# gravador.net
KiCad netlist of a schematic drawn in EAGLE
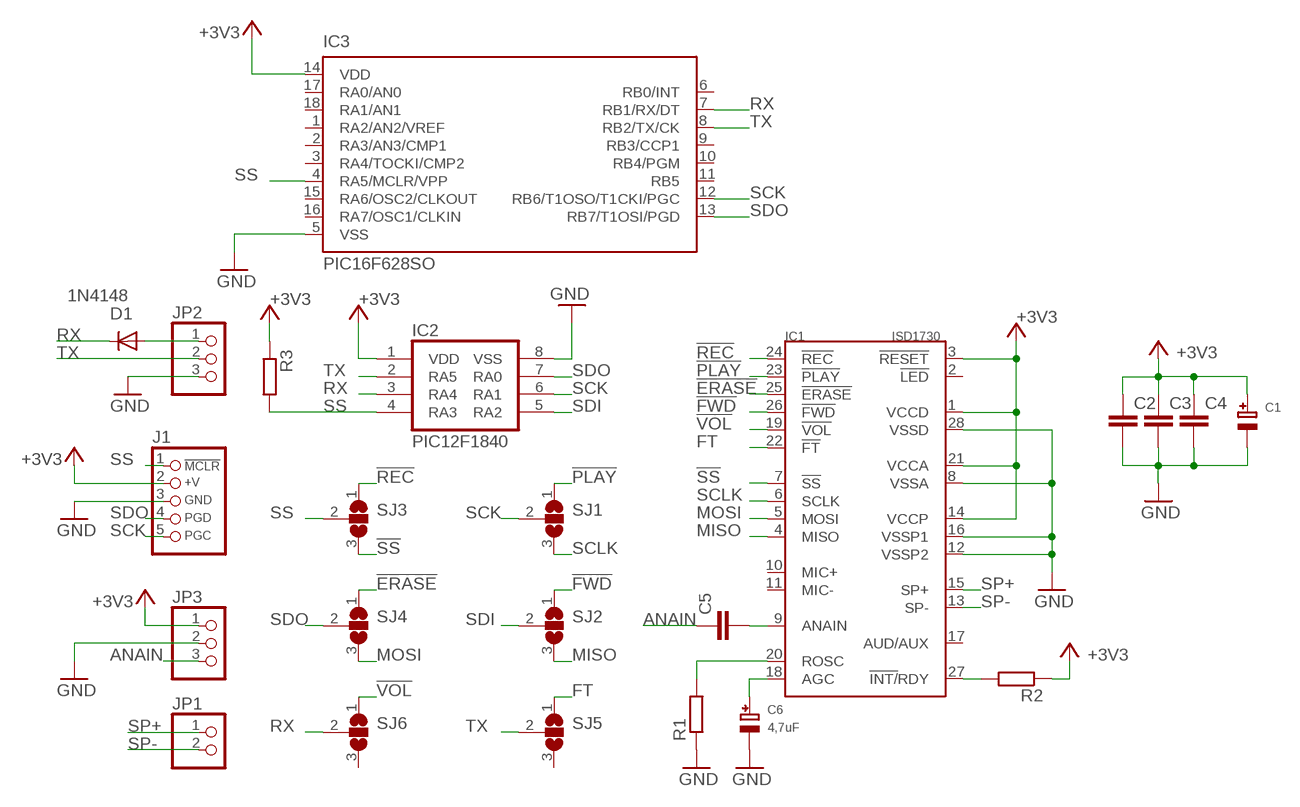
[diagram p0: schematic, sheet 1]

(export (version "E")
  (design (tool "Eeschema 10.0.6"))
  (components
    (comp (ref "C1")
      (value "CAP_ELECTROLYTICPTH_3.5MMGRID_8MMDIA")
      (footprint "eagle-import:CELEC_3.5MM_8MM")
      (libsource (lib "eagle-import") (part "CAP_ELECTROLYTICPTH_3.5MMGRID_8MMDIA"))
    )
    (comp (ref "C2")
      (value "C-EU025-025X050")
      (footprint "eagle-import:C025-025X050")
      (libsource (lib "eagle-import") (part "C-EU025-025X050"))
    )
    (comp (ref "C3")
      (value "C-EU025-025X050")
      (footprint "eagle-import:C025-025X050")
      (libsource (lib "eagle-import") (part "C-EU025-025X050"))
    )
    (comp (ref "C4")
      (value "C-EU025-025X050")
      (footprint "eagle-import:C025-025X050")
      (libsource (lib "eagle-import") (part "C-EU025-025X050"))
    )
    (comp (ref "C5")
      (value "C-EU025-025X050")
      (footprint "eagle-import:C025-025X050")
      (libsource (lib "eagle-import") (part "C-EU025-025X050"))
    )
    (comp (ref "C6")
      (value "4,7uF")
      (footprint "eagle-import:CELEC_3.5MM_8MM")
      (libsource (lib "eagle-import") (part "CAP_ELECTROLYTICPTH_3.5MMGRID_8MMDIA"))
    )
    (comp (ref "D1")
      (value "1N4148")
      (footprint "eagle-import:DO35-7")
      (libsource (lib "eagle-import") (part "1N4148DO35-7"))
    )
    (comp (ref "IC1")
      (value "ISD1730")
      (footprint "eagle-import:SOP28_300MIL")
      (libsource (lib "eagle-import") (part "ISD1730"))
    )
    (comp (ref "IC2")
      (value "PIC12F1840")
      (footprint "eagle-import:DFN6_3X3")
      (libsource (lib "eagle-import") (part "IC_UC_PIC12F1822DFN6_3X3"))
    )
    (comp (ref "IC3")
      (value "PIC16F628SO")
      (footprint "eagle-import:SO-18W")
      (fields (field (name "MF") "MICROCHIP") (field (name "MPN") "PIC16F628-20I/SO"))
      (libsource (lib "eagle-import") (part "PIC16F62SO8"))
    )
    (comp (ref "J1")
      (value "CON_HEADER_PRG_PIC_ICSP0.1INCH_B")
      (footprint "eagle-import:HEADER_PRG_1X05_ICSP_B")
      (libsource (lib "eagle-import") (part "CON_HEADER_PRG_PIC_ICSP0.1INCH_B"))
    )
    (comp (ref "JP1")
      (value "PINHD-1X2")
      (footprint "eagle-import:1X02")
      (libsource (lib "eagle-import") (part "PINHD-1X2"))
    )
    (comp (ref "JP2")
      (value "PINHD-1X3")
      (footprint "eagle-import:1X03")
      (libsource (lib "eagle-import") (part "PINHD-1X3"))
    )
    (comp (ref "JP3")
      (value "PINHD-1X3")
      (footprint "eagle-import:1X03")
      (libsource (lib "eagle-import") (part "PINHD-1X3"))
    )
    (comp (ref "R1")
      (value "R-EU_0204/2V")
      (footprint "eagle-import:0204V")
      (libsource (lib "eagle-import") (part "R-EU_0204/2V"))
    )
    (comp (ref "R2")
      (value "R-EU_0204/2V")
      (footprint "eagle-import:0204V")
      (libsource (lib "eagle-import") (part "R-EU_0204/2V"))
    )
    (comp (ref "R3")
      (value "R-EU_0204/2V")
      (footprint "eagle-import:0204V")
      (libsource (lib "eagle-import") (part "R-EU_0204/2V"))
    )
    (comp (ref "SJ1")
      (value "SJ2W")
      (footprint "eagle-import:SJ_2")
      (libsource (lib "eagle-import") (part "SJ2W"))
    )
    (comp (ref "SJ2")
      (value "SJ2W")
      (footprint "eagle-import:SJ_2")
      (libsource (lib "eagle-import") (part "SJ2W"))
    )
    (comp (ref "SJ3")
      (value "SJ2W")
      (footprint "eagle-import:SJ_2")
      (libsource (lib "eagle-import") (part "SJ2W"))
    )
    (comp (ref "SJ4")
      (value "SJ2W")
      (footprint "eagle-import:SJ_2")
      (libsource (lib "eagle-import") (part "SJ2W"))
    )
    (comp (ref "SJ5")
      (value "SJ2W")
      (footprint "eagle-import:SJ_2")
      (libsource (lib "eagle-import") (part "SJ2W"))
    )
    (comp (ref "SJ6")
      (value "SJ2W")
      (footprint "eagle-import:SJ_2")
      (libsource (lib "eagle-import") (part "SJ2W"))
    )
  )
  (nets
    (net (code "1") (name "+3V3") (class "Default")
      (node (ref "C1") (pin "+") (pinfunction "+_+") (pintype "passive"))
      (node (ref "C2") (pin "1") (pinfunction "1_1") (pintype "passive"))
      (node (ref "C3") (pin "1") (pinfunction "1_1") (pintype "passive"))
      (node (ref "C4") (pin "1") (pinfunction "1_1") (pintype "passive"))
      (node (ref "IC1") (pin "1") (pinfunction "VCCD_1") (pintype "power_in"))
      (node (ref "IC1") (pin "14") (pinfunction "VCCP_14") (pintype "power_in"))
      (node (ref "IC1") (pin "21") (pinfunction "VCCA_21") (pintype "power_in"))
      (node (ref "IC1") (pin "3") (pinfunction "~{RESET}_3") (pintype "bidirectional"))
      (node (ref "IC2") (pin "1") (pinfunction "VDD_1") (pintype "power_in"))
      (node (ref "IC3") (pin "14") (pinfunction "VDD_14") (pintype "power_in"))
      (node (ref "J1") (pin "2") (pinfunction "+V_2") (pintype "passive"))
      (node (ref "JP3") (pin "1") (pinfunction "1_1") (pintype "passive"))
      (node (ref "R2") (pin "1") (pinfunction "1_1") (pintype "passive"))
      (node (ref "R3") (pin "1") (pinfunction "1_1") (pintype "passive"))
    )
    (net (code "2") (name "/ANAIN") (class "Default")
      (node (ref "C5") (pin "1") (pinfunction "1_1") (pintype "passive"))
      (node (ref "JP3") (pin "3") (pinfunction "3_3") (pintype "passive"))
    )
    (net (code "3") (name "/FT") (class "Default")
      (node (ref "IC1") (pin "22") (pinfunction "~{FT}_22") (pintype "bidirectional"))
      (node (ref "SJ5") (pin "1") (pinfunction "1_1") (pintype "passive"))
    )
    (net (code "4") (name "/MISO") (class "Default")
      (node (ref "IC1") (pin "4") (pinfunction "MISO_4") (pintype "bidirectional"))
      (node (ref "SJ2") (pin "3") (pinfunction "3_3") (pintype "passive"))
    )
    (net (code "5") (name "/MOSI") (class "Default")
      (node (ref "IC1") (pin "5") (pinfunction "MOSI_5") (pintype "bidirectional"))
      (node (ref "SJ4") (pin "3") (pinfunction "3_3") (pintype "passive"))
    )
    (net (code "6") (name "/RX") (class "Default")
      (node (ref "D1") (pin "C") (pinfunction "C_C") (pintype "passive"))
      (node (ref "IC2") (pin "3") (pinfunction "RA4_3") (pintype "bidirectional"))
      (node (ref "IC3") (pin "7") (pinfunction "RB1/RX/DT_7") (pintype "bidirectional"))
      (node (ref "SJ6") (pin "2") (pinfunction "2_2") (pintype "passive"))
    )
    (net (code "7") (name "/SCK") (class "Default")
      (node (ref "IC2") (pin "6") (pinfunction "RA1_6") (pintype "bidirectional"))
      (node (ref "IC3") (pin "12") (pinfunction "RB6/T1OSO/T1CKI/PGC_12") (pintype "bidirectional"))
      (node (ref "J1") (pin "5") (pinfunction "PGC_5") (pintype "passive"))
      (node (ref "SJ1") (pin "2") (pinfunction "2_2") (pintype "passive"))
    )
    (net (code "8") (name "/SCLK") (class "Default")
      (node (ref "IC1") (pin "6") (pinfunction "SCLK_6") (pintype "bidirectional"))
      (node (ref "SJ1") (pin "3") (pinfunction "3_3") (pintype "passive"))
    )
    (net (code "9") (name "/SDI") (class "Default")
      (node (ref "IC2") (pin "5") (pinfunction "RA2_5") (pintype "bidirectional"))
      (node (ref "SJ2") (pin "2") (pinfunction "2_2") (pintype "passive"))
    )
    (net (code "10") (name "/SDO") (class "Default")
      (node (ref "IC2") (pin "7") (pinfunction "RA0_7") (pintype "bidirectional"))
      (node (ref "IC3") (pin "13") (pinfunction "RB7/T1OSI/PGD_13") (pintype "bidirectional"))
      (node (ref "J1") (pin "4") (pinfunction "PGD_4") (pintype "passive"))
      (node (ref "SJ4") (pin "2") (pinfunction "2_2") (pintype "passive"))
    )
    (net (code "11") (name "/SP+") (class "Default")
      (node (ref "IC1") (pin "15") (pinfunction "SP+_15") (pintype "bidirectional"))
      (node (ref "JP1") (pin "1") (pinfunction "1_1") (pintype "passive"))
    )
    (net (code "12") (name "/SP-") (class "Default")
      (node (ref "IC1") (pin "13") (pinfunction "SP-_13") (pintype "bidirectional"))
      (node (ref "JP1") (pin "2") (pinfunction "2_2") (pintype "passive"))
    )
    (net (code "13") (name "/SS") (class "Default")
      (node (ref "IC2") (pin "4") (pinfunction "RA3_4") (pintype "bidirectional"))
      (node (ref "IC3") (pin "4") (pinfunction "RA5/MCLR/VPP_4") (pintype "bidirectional"))
      (node (ref "J1") (pin "1") (pinfunction "/MCLR_1") (pintype "passive"))
      (node (ref "R3") (pin "2") (pinfunction "2_2") (pintype "passive"))
      (node (ref "SJ3") (pin "2") (pinfunction "2_2") (pintype "passive"))
    )
    (net (code "14") (name "/TX") (class "Default")
      (node (ref "IC2") (pin "2") (pinfunction "RA5_2") (pintype "bidirectional"))
      (node (ref "IC3") (pin "8") (pinfunction "RB2/TX/CK_8") (pintype "bidirectional"))
      (node (ref "JP2") (pin "2") (pinfunction "2_2") (pintype "passive"))
      (node (ref "SJ5") (pin "2") (pinfunction "2_2") (pintype "passive"))
    )
    (net (code "15") (name "/~{ERASE}") (class "Default")
      (node (ref "IC1") (pin "25") (pinfunction "~{ERASE}_25") (pintype "bidirectional"))
      (node (ref "SJ4") (pin "1") (pinfunction "1_1") (pintype "passive"))
    )
    (net (code "16") (name "/~{FWD}") (class "Default")
      (node (ref "IC1") (pin "26") (pinfunction "~{FWD}_26") (pintype "bidirectional"))
      (node (ref "SJ2") (pin "1") (pinfunction "1_1") (pintype "passive"))
    )
    (net (code "17") (name "/~{PLAY}") (class "Default")
      (node (ref "IC1") (pin "23") (pinfunction "~{PLAY}_23") (pintype "bidirectional"))
      (node (ref "SJ1") (pin "1") (pinfunction "1_1") (pintype "passive"))
    )
    (net (code "18") (name "/~{REC}") (class "Default")
      (node (ref "IC1") (pin "24") (pinfunction "~{REC}_24") (pintype "bidirectional"))
      (node (ref "SJ3") (pin "1") (pinfunction "1_1") (pintype "passive"))
    )
    (net (code "19") (name "/~{SS}") (class "Default")
      (node (ref "IC1") (pin "7") (pinfunction "~{SS}_7") (pintype "bidirectional"))
      (node (ref "SJ3") (pin "3") (pinfunction "3_3") (pintype "passive"))
    )
    (net (code "20") (name "/~{VOL}") (class "Default")
      (node (ref "IC1") (pin "19") (pinfunction "~{VOL}_19") (pintype "bidirectional"))
      (node (ref "SJ6") (pin "1") (pinfunction "1_1") (pintype "passive"))
    )
    (net (code "21") (name "GND") (class "Default")
      (node (ref "C1") (pin "-") (pinfunction "-_-") (pintype "passive"))
      (node (ref "C2") (pin "2") (pinfunction "2_2") (pintype "passive"))
      (node (ref "C3") (pin "2") (pinfunction "2_2") (pintype "passive"))
      (node (ref "C4") (pin "2") (pinfunction "2_2") (pintype "passive"))
      (node (ref "C6") (pin "-") (pinfunction "-_-") (pintype "passive"))
      (node (ref "IC1") (pin "12") (pinfunction "VSSP2_12") (pintype "power_in"))
      (node (ref "IC1") (pin "16") (pinfunction "VSSP1_16") (pintype "power_in"))
      (node (ref "IC1") (pin "28") (pinfunction "VSSD_28") (pintype "power_in"))
      (node (ref "IC1") (pin "8") (pinfunction "VSSA_8") (pintype "power_in"))
      (node (ref "IC2") (pin "8") (pinfunction "VSS_8") (pintype "power_in"))
      (node (ref "IC3") (pin "5") (pinfunction "VSS_5") (pintype "power_in"))
      (node (ref "J1") (pin "3") (pinfunction "GND_3") (pintype "passive"))
      (node (ref "JP2") (pin "3") (pinfunction "3_3") (pintype "passive"))
      (node (ref "JP3") (pin "2") (pinfunction "2_2") (pintype "passive"))
      (node (ref "R1") (pin "1") (pinfunction "1_1") (pintype "passive"))
    )
    (net (code "22") (name "Net-(D1-PadA)") (class "Default")
      (node (ref "D1") (pin "A") (pinfunction "A_A") (pintype "passive"))
      (node (ref "JP2") (pin "1") (pinfunction "1_1") (pintype "passive"))
    )
    (net (code "23") (name "Net-(IC1-AGC)") (class "Default")
      (node (ref "C6") (pin "+") (pinfunction "+_+") (pintype "passive"))
      (node (ref "IC1") (pin "18") (pinfunction "AGC_18") (pintype "bidirectional"))
    )
    (net (code "24") (name "Net-(IC1-ANAIN)") (class "Default")
      (node (ref "C5") (pin "2") (pinfunction "2_2") (pintype "passive"))
      (node (ref "IC1") (pin "9") (pinfunction "ANAIN_9") (pintype "bidirectional"))
    )
    (net (code "25") (name "Net-(IC1-ROSC)") (class "Default")
      (node (ref "IC1") (pin "20") (pinfunction "ROSC_20") (pintype "bidirectional"))
      (node (ref "R1") (pin "2") (pinfunction "2_2") (pintype "passive"))
    )
    (net (code "26") (name "Net-(IC1-~{INT{slash}}RDY)") (class "Default")
      (node (ref "IC1") (pin "27") (pinfunction "~{INT/}RDY_27") (pintype "bidirectional"))
      (node (ref "R2") (pin "2") (pinfunction "2_2") (pintype "passive"))
    )
    (net (code "27") (name "unconnected-(IC1-AUD{slash}AUX-Pad17)") (class "Default")
      (node (ref "IC1") (pin "17") (pinfunction "AUD/AUX_17") (pintype "bidirectional"))
    )
    (net (code "28") (name "unconnected-(IC1-MIC+-Pad10)") (class "Default")
      (node (ref "IC1") (pin "10") (pinfunction "MIC+_10") (pintype "bidirectional"))
    )
    (net (code "29") (name "unconnected-(IC1-MIC--Pad11)") (class "Default")
      (node (ref "IC1") (pin "11") (pinfunction "MIC-_11") (pintype "bidirectional"))
    )
    (net (code "30") (name "unconnected-(IC1-~{LED}-Pad2)") (class "Default")
      (node (ref "IC1") (pin "2") (pinfunction "~{LED}_2") (pintype "bidirectional"))
    )
    (net (code "31") (name "unconnected-(IC3-RA0{slash}AN0-Pad17)") (class "Default")
      (node (ref "IC3") (pin "17") (pinfunction "RA0/AN0_17") (pintype "bidirectional"))
    )
    (net (code "32") (name "unconnected-(IC3-RA1{slash}AN1-Pad18)") (class "Default")
      (node (ref "IC3") (pin "18") (pinfunction "RA1/AN1_18") (pintype "bidirectional"))
    )
    (net (code "33") (name "unconnected-(IC3-RA2{slash}AN2{slash}VREF-Pad1)") (class "Default")
      (node (ref "IC3") (pin "1") (pinfunction "RA2/AN2/VREF_1") (pintype "bidirectional"))
    )
    (net (code "34") (name "unconnected-(IC3-RA3{slash}AN3{slash}CMP1-Pad2)") (class "Default")
      (node (ref "IC3") (pin "2") (pinfunction "RA3/AN3/CMP1_2") (pintype "bidirectional"))
    )
    (net (code "35") (name "unconnected-(IC3-RA4{slash}TOCKI{slash}CMP2-Pad3)") (class "Default")
      (node (ref "IC3") (pin "3") (pinfunction "RA4/TOCKI/CMP2_3") (pintype "bidirectional"))
    )
    (net (code "36") (name "unconnected-(IC3-RA6{slash}OSC2{slash}CLKOUT-Pad15)") (class "Default")
      (node (ref "IC3") (pin "15") (pinfunction "RA6/OSC2/CLKOUT_15") (pintype "bidirectional"))
    )
    (net (code "37") (name "unconnected-(IC3-RA7{slash}OSC1{slash}CLKIN-Pad16)") (class "Default")
      (node (ref "IC3") (pin "16") (pinfunction "RA7/OSC1/CLKIN_16") (pintype "bidirectional"))
    )
    (net (code "38") (name "unconnected-(IC3-RB0{slash}INT-Pad6)") (class "Default")
      (node (ref "IC3") (pin "6") (pinfunction "RB0/INT_6") (pintype "bidirectional"))
    )
    (net (code "39") (name "unconnected-(IC3-RB3{slash}CCP1-Pad9)") (class "Default")
      (node (ref "IC3") (pin "9") (pinfunction "RB3/CCP1_9") (pintype "bidirectional"))
    )
    (net (code "40") (name "unconnected-(IC3-RB4{slash}PGM-Pad10)") (class "Default")
      (node (ref "IC3") (pin "10") (pinfunction "RB4/PGM_10") (pintype "bidirectional"))
    )
    (net (code "41") (name "unconnected-(IC3-RB5-Pad11)") (class "Default")
      (node (ref "IC3") (pin "11") (pinfunction "RB5_11") (pintype "bidirectional"))
    )
    (net (code "42") (name "unconnected-(SJ5-Pad3)") (class "Default")
      (node (ref "SJ5") (pin "3") (pinfunction "3_3") (pintype "passive"))
    )
    (net (code "43") (name "unconnected-(SJ6-Pad3)") (class "Default")
      (node (ref "SJ6") (pin "3") (pinfunction "3_3") (pintype "passive"))
    )
  )
)
